# RC_Engine_Sound_ESP32.net
KiCad netlist of a schematic drawn in EAGLE
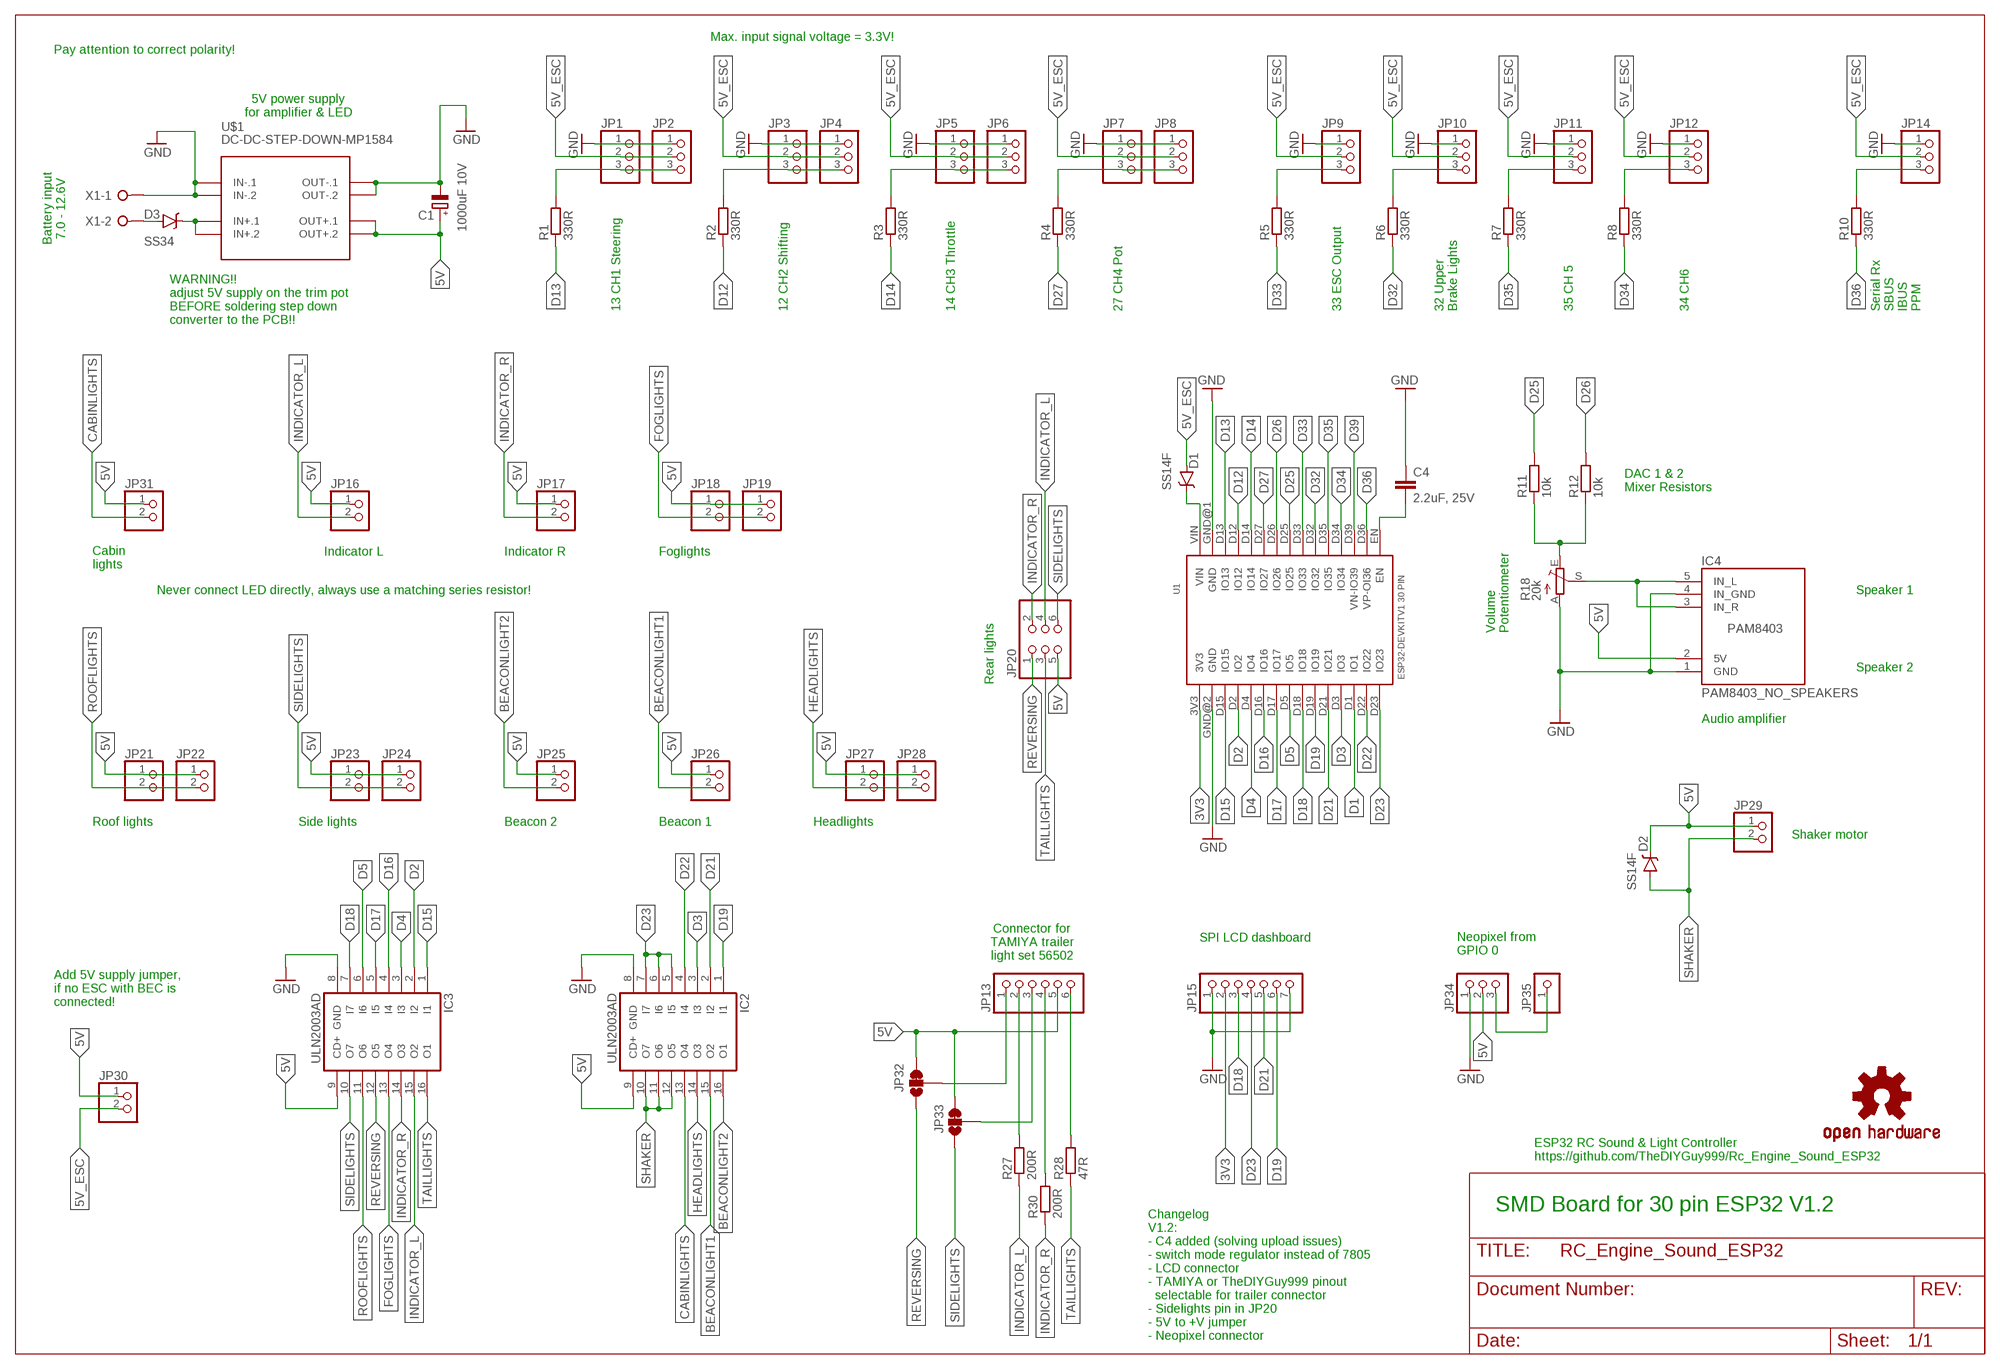
[diagram p0: schematic, sheet 1]

(export (version "E")
  (design (tool "Eeschema 10.0.6"))
  (components
    (comp (ref "C1")
      (value "1000uF 10V")
      (footprint "eagle-import:UD-10X10_NICHICON")
      (libsource (lib "eagle-import") (part "CPOL-EUUD-10X10"))
    )
    (comp (ref "C4")
      (value "2.2uF, 25V")
      (footprint "eagle-import:C1206")
      (libsource (lib "eagle-import") (part "C-EUC1206"))
    )
    (comp (ref "D1")
      (value "SS14F")
      (footprint "eagle-import:SMA-DIODE")
      (libsource (lib "eagle-import") (part "MBRA140"))
    )
    (comp (ref "D2")
      (value "SS14F")
      (footprint "eagle-import:SMA-DIODE")
      (libsource (lib "eagle-import") (part "MBRA140"))
    )
    (comp (ref "D3")
      (value "SS34")
      (footprint "eagle-import:SMA-DIODE")
      (libsource (lib "eagle-import") (part "MBRA140"))
    )
    (comp (ref "IC2")
      (value "ULN2003AD")
      (footprint "eagle-import:SO16")
      (libsource (lib "eagle-import") (part "ULN2003AD"))
    )
    (comp (ref "IC3")
      (value "ULN2003AD")
      (footprint "eagle-import:SO16")
      (libsource (lib "eagle-import") (part "ULN2003AD"))
    )
    (comp (ref "IC4")
      (value "PAM8403_NO_SPEAKERS")
      (footprint "eagle-import:PAM8403_NO_SPEAKERS")
      (libsource (lib "eagle-import") (part "PAM8403_NO_SPEAKERS"))
    )
    (comp (ref "JP1")
      (value "PINHD-1X3")
      (footprint "eagle-import:1X03")
      (libsource (lib "eagle-import") (part "PINHD-1X3"))
    )
    (comp (ref "JP2")
      (value "PINHD-1X3")
      (footprint "eagle-import:1X03")
      (libsource (lib "eagle-import") (part "PINHD-1X3"))
    )
    (comp (ref "JP3")
      (value "PINHD-1X3")
      (footprint "eagle-import:1X03")
      (libsource (lib "eagle-import") (part "PINHD-1X3"))
    )
    (comp (ref "JP4")
      (value "PINHD-1X3")
      (footprint "eagle-import:1X03")
      (libsource (lib "eagle-import") (part "PINHD-1X3"))
    )
    (comp (ref "JP5")
      (value "PINHD-1X3")
      (footprint "eagle-import:1X03")
      (libsource (lib "eagle-import") (part "PINHD-1X3"))
    )
    (comp (ref "JP6")
      (value "PINHD-1X3")
      (footprint "eagle-import:1X03")
      (libsource (lib "eagle-import") (part "PINHD-1X3"))
    )
    (comp (ref "JP7")
      (value "PINHD-1X3")
      (footprint "eagle-import:1X03")
      (libsource (lib "eagle-import") (part "PINHD-1X3"))
    )
    (comp (ref "JP8")
      (value "PINHD-1X3")
      (footprint "eagle-import:1X03")
      (libsource (lib "eagle-import") (part "PINHD-1X3"))
    )
    (comp (ref "JP9")
      (value "PINHD-1X3")
      (footprint "eagle-import:1X03")
      (libsource (lib "eagle-import") (part "PINHD-1X3"))
    )
    (comp (ref "JP10")
      (value "PINHD-1X3")
      (footprint "eagle-import:1X03")
      (libsource (lib "eagle-import") (part "PINHD-1X3"))
    )
    (comp (ref "JP11")
      (value "PINHD-1X3")
      (footprint "eagle-import:1X03")
      (libsource (lib "eagle-import") (part "PINHD-1X3"))
    )
    (comp (ref "JP12")
      (value "PINHD-1X3")
      (footprint "eagle-import:1X03")
      (libsource (lib "eagle-import") (part "PINHD-1X3"))
    )
    (comp (ref "JP13")
      (value "PINHD-1X6")
      (footprint "eagle-import:1X06")
      (libsource (lib "eagle-import") (part "PINHD-1X6"))
    )
    (comp (ref "JP14")
      (value "PINHD-1X3")
      (footprint "eagle-import:1X03")
      (libsource (lib "eagle-import") (part "PINHD-1X3"))
    )
    (comp (ref "JP15")
      (value "PINHD-1X7")
      (footprint "eagle-import:1X07")
      (libsource (lib "eagle-import") (part "PINHD-1X7"))
    )
    (comp (ref "JP16")
      (value "PINHD-1X2")
      (footprint "eagle-import:1X02")
      (libsource (lib "eagle-import") (part "PINHD-1X2"))
    )
    (comp (ref "JP17")
      (value "PINHD-1X2")
      (footprint "eagle-import:1X02")
      (libsource (lib "eagle-import") (part "PINHD-1X2"))
    )
    (comp (ref "JP18")
      (value "PINHD-1X2")
      (footprint "eagle-import:1X02")
      (libsource (lib "eagle-import") (part "PINHD-1X2"))
    )
    (comp (ref "JP19")
      (value "PINHD-1X2")
      (footprint "eagle-import:1X02")
      (libsource (lib "eagle-import") (part "PINHD-1X2"))
    )
    (comp (ref "JP20")
      (value "PINHD-2X3")
      (footprint "eagle-import:2X03")
      (libsource (lib "eagle-import") (part "PINHD-2X3"))
    )
    (comp (ref "JP21")
      (value "PINHD-1X2")
      (footprint "eagle-import:1X02")
      (libsource (lib "eagle-import") (part "PINHD-1X2"))
    )
    (comp (ref "JP22")
      (value "PINHD-1X2")
      (footprint "eagle-import:1X02")
      (libsource (lib "eagle-import") (part "PINHD-1X2"))
    )
    (comp (ref "JP23")
      (value "PINHD-1X2")
      (footprint "eagle-import:1X02")
      (libsource (lib "eagle-import") (part "PINHD-1X2"))
    )
    (comp (ref "JP24")
      (value "PINHD-1X2")
      (footprint "eagle-import:1X02")
      (libsource (lib "eagle-import") (part "PINHD-1X2"))
    )
    (comp (ref "JP25")
      (value "PINHD-1X2")
      (footprint "eagle-import:1X02")
      (libsource (lib "eagle-import") (part "PINHD-1X2"))
    )
    (comp (ref "JP26")
      (value "PINHD-1X2")
      (footprint "eagle-import:1X02")
      (libsource (lib "eagle-import") (part "PINHD-1X2"))
    )
    (comp (ref "JP27")
      (value "PINHD-1X2")
      (footprint "eagle-import:1X02")
      (libsource (lib "eagle-import") (part "PINHD-1X2"))
    )
    (comp (ref "JP28")
      (value "PINHD-1X2")
      (footprint "eagle-import:1X02")
      (libsource (lib "eagle-import") (part "PINHD-1X2"))
    )
    (comp (ref "JP29")
      (value "PINHD-1X2")
      (footprint "eagle-import:1X02")
      (libsource (lib "eagle-import") (part "PINHD-1X2"))
    )
    (comp (ref "JP30")
      (value "PINHD-1X2")
      (footprint "eagle-import:1X02")
      (libsource (lib "eagle-import") (part "PINHD-1X2"))
    )
    (comp (ref "JP31")
      (value "PINHD-1X2")
      (footprint "eagle-import:1X02")
      (libsource (lib "eagle-import") (part "PINHD-1X2"))
    )
    (comp (ref "JP32")
      (value "JUMPER-PAD-3-2OF3_NC_BY_TRACE_LARGE")
      (footprint "eagle-import:PAD-JUMPER-3-2OF3_NC_BY_TRACE_YES_SILK_LARGE")
      (libsource (lib "eagle-import") (part "JUMPER-PAD-3-2OF3_NC_BY_TRACE_LARGE"))
    )
    (comp (ref "JP33")
      (value "JUMPER-PAD-3-2OF3_NC_BY_TRACE_LARGE")
      (footprint "eagle-import:PAD-JUMPER-3-2OF3_NC_BY_TRACE_YES_SILK_LARGE")
      (libsource (lib "eagle-import") (part "JUMPER-PAD-3-2OF3_NC_BY_TRACE_LARGE"))
    )
    (comp (ref "JP34")
      (value "PINHD-1X3")
      (footprint "eagle-import:1X03")
      (libsource (lib "eagle-import") (part "PINHD-1X3"))
    )
    (comp (ref "JP35")
      (value "PINHD-1X1")
      (footprint "eagle-import:1X01")
      (libsource (lib "eagle-import") (part "PINHD-1X1"))
    )
    (comp (ref "LOGO1")
      (value "OSHW-LOGOM")
      (footprint "eagle-import:OSHW-LOGO-M")
      (libsource (lib "eagle-import") (part "OSHW-LOGOM"))
    )
    (comp (ref "R1")
      (value "330R")
      (footprint "eagle-import:R0805")
      (libsource (lib "eagle-import") (part "R-EU_R0805"))
    )
    (comp (ref "R2")
      (value "330R")
      (footprint "eagle-import:R0805")
      (libsource (lib "eagle-import") (part "R-EU_R0805"))
    )
    (comp (ref "R3")
      (value "330R")
      (footprint "eagle-import:R0805")
      (libsource (lib "eagle-import") (part "R-EU_R0805"))
    )
    (comp (ref "R4")
      (value "330R")
      (footprint "eagle-import:R0805")
      (libsource (lib "eagle-import") (part "R-EU_R0805"))
    )
    (comp (ref "R5")
      (value "330R")
      (footprint "eagle-import:R0805")
      (libsource (lib "eagle-import") (part "R-EU_R0805"))
    )
    (comp (ref "R6")
      (value "330R")
      (footprint "eagle-import:R0805")
      (libsource (lib "eagle-import") (part "R-EU_R0805"))
    )
    (comp (ref "R7")
      (value "330R")
      (footprint "eagle-import:R0805")
      (libsource (lib "eagle-import") (part "R-EU_R0805"))
    )
    (comp (ref "R8")
      (value "330R")
      (footprint "eagle-import:R0805")
      (libsource (lib "eagle-import") (part "R-EU_R0805"))
    )
    (comp (ref "R10")
      (value "330R")
      (footprint "eagle-import:R0805")
      (libsource (lib "eagle-import") (part "R-EU_R0805"))
    )
    (comp (ref "R11")
      (value "10k")
      (footprint "eagle-import:R0805")
      (libsource (lib "eagle-import") (part "R-EU_R0805"))
    )
    (comp (ref "R12")
      (value "10k")
      (footprint "eagle-import:R0805")
      (libsource (lib "eagle-import") (part "R-EU_R0805"))
    )
    (comp (ref "R18")
      (value "20k")
      (footprint "eagle-import:S64W")
      (libsource (lib "eagle-import") (part "TRIM_EU-S64W"))
    )
    (comp (ref "R27")
      (value "200R")
      (footprint "eagle-import:R0805")
      (libsource (lib "eagle-import") (part "R-EU_R0805"))
    )
    (comp (ref "R28")
      (value "47R")
      (footprint "eagle-import:R0805")
      (libsource (lib "eagle-import") (part "R-EU_R0805"))
    )
    (comp (ref "R30")
      (value "200R")
      (footprint "eagle-import:R0805")
      (libsource (lib "eagle-import") (part "R-EU_R0805"))
    )
    (comp (ref "U$1")
      (value "DC-DC-STEP-DOWN-MP1584")
      (footprint "eagle-import:DC-DC-STEP-DOWN-MP1584")
      (libsource (lib "eagle-import") (part "DC-DC-STEP-DOWN-MP1584"))
    )
    (comp (ref "U1")
      (value "ESP32DEVKITV1")
      (footprint "eagle-import:ESP32-DEVKITV1")
      (libsource (lib "eagle-import") (part "ESP32DEVKITV1"))
    )
    (comp (ref "X1")
      (value "W237-02P")
      (footprint "eagle-import:W237-132")
      (libsource (lib "eagle-import") (part "W237-02P"))
    )
  )
  (nets
    (net (code "1") (name "3V3") (class "Default")
      (node (ref "JP15") (pin "2") (pinfunction "2_2") (pintype "passive"))
      (node (ref "U1") (pin "3V3") (pinfunction "3V3_3V3") (pintype "power_in"))
    )
    (net (code "2") (name "5V") (class "Default")
      (node (ref "C1") (pin "+") (pinfunction "+_+") (pintype "passive"))
      (node (ref "D2") (pin "C") (pinfunction "C_C") (pintype "passive"))
      (node (ref "IC2") (pin "9") (pinfunction "CD+_9") (pintype "passive"))
      (node (ref "IC3") (pin "9") (pinfunction "CD+_9") (pintype "passive"))
      (node (ref "IC4") (pin "2") (pinfunction "5V_2") (pintype "input"))
      (node (ref "JP13") (pin "5") (pinfunction "5_5") (pintype "passive"))
      (node (ref "JP16") (pin "1") (pinfunction "1_1") (pintype "passive"))
      (node (ref "JP17") (pin "1") (pinfunction "1_1") (pintype "passive"))
      (node (ref "JP18") (pin "1") (pinfunction "1_1") (pintype "passive"))
      (node (ref "JP19") (pin "1") (pinfunction "1_1") (pintype "passive"))
      (node (ref "JP20") (pin "5") (pinfunction "5_5") (pintype "passive"))
      (node (ref "JP21") (pin "1") (pinfunction "1_1") (pintype "passive"))
      (node (ref "JP22") (pin "1") (pinfunction "1_1") (pintype "passive"))
      (node (ref "JP23") (pin "1") (pinfunction "1_1") (pintype "passive"))
      (node (ref "JP24") (pin "1") (pinfunction "1_1") (pintype "passive"))
      (node (ref "JP25") (pin "1") (pinfunction "1_1") (pintype "passive"))
      (node (ref "JP26") (pin "1") (pinfunction "1_1") (pintype "passive"))
      (node (ref "JP27") (pin "1") (pinfunction "1_1") (pintype "passive"))
      (node (ref "JP28") (pin "1") (pinfunction "1_1") (pintype "passive"))
      (node (ref "JP29") (pin "1") (pinfunction "1_1") (pintype "passive"))
      (node (ref "JP30") (pin "1") (pinfunction "1_1") (pintype "passive"))
      (node (ref "JP31") (pin "1") (pinfunction "1_1") (pintype "passive"))
      (node (ref "JP32") (pin "3") (pinfunction "3_3") (pintype "passive"))
      (node (ref "JP33") (pin "3") (pinfunction "3_3") (pintype "passive"))
      (node (ref "JP34") (pin "2") (pinfunction "2_2") (pintype "passive"))
      (node (ref "U$1") (pin "OUT+.1") (pinfunction "OUT+.1_OUT+.1") (pintype "bidirectional"))
      (node (ref "U$1") (pin "OUT+.2") (pinfunction "OUT+.2_OUT+.2") (pintype "bidirectional"))
    )
    (net (code "3") (name "5V_ESC") (class "Default")
      (node (ref "D1") (pin "A") (pinfunction "A_A") (pintype "passive"))
      (node (ref "JP1") (pin "2") (pinfunction "2_2") (pintype "passive"))
      (node (ref "JP10") (pin "2") (pinfunction "2_2") (pintype "passive"))
      (node (ref "JP11") (pin "2") (pinfunction "2_2") (pintype "passive"))
      (node (ref "JP12") (pin "2") (pinfunction "2_2") (pintype "passive"))
      (node (ref "JP14") (pin "2") (pinfunction "2_2") (pintype "passive"))
      (node (ref "JP2") (pin "2") (pinfunction "2_2") (pintype "passive"))
      (node (ref "JP3") (pin "2") (pinfunction "2_2") (pintype "passive"))
      (node (ref "JP30") (pin "2") (pinfunction "2_2") (pintype "passive"))
      (node (ref "JP4") (pin "2") (pinfunction "2_2") (pintype "passive"))
      (node (ref "JP5") (pin "2") (pinfunction "2_2") (pintype "passive"))
      (node (ref "JP6") (pin "2") (pinfunction "2_2") (pintype "passive"))
      (node (ref "JP7") (pin "2") (pinfunction "2_2") (pintype "passive"))
      (node (ref "JP8") (pin "2") (pinfunction "2_2") (pintype "passive"))
      (node (ref "JP9") (pin "2") (pinfunction "2_2") (pintype "passive"))
    )
    (net (code "4") (name "BEACONLIGHT1") (class "Default")
      (node (ref "IC2") (pin "15") (pinfunction "O2_15") (pintype "open_collector"))
      (node (ref "JP26") (pin "2") (pinfunction "2_2") (pintype "passive"))
    )
    (net (code "5") (name "BEACONLIGHT2") (class "Default")
      (node (ref "IC2") (pin "16") (pinfunction "O1_16") (pintype "open_collector"))
      (node (ref "JP25") (pin "2") (pinfunction "2_2") (pintype "passive"))
    )
    (net (code "6") (name "CABINLIGHTS") (class "Default")
      (node (ref "IC2") (pin "13") (pinfunction "O4_13") (pintype "open_collector"))
      (node (ref "JP31") (pin "2") (pinfunction "2_2") (pintype "passive"))
    )
    (net (code "7") (name "D1") (class "Default")
      (node (ref "U1") (pin "D1") (pinfunction "IO1_D1") (pintype "bidirectional"))
    )
    (net (code "8") (name "D2") (class "Default")
      (node (ref "IC3") (pin "2") (pinfunction "I2_2") (pintype "input"))
      (node (ref "U1") (pin "D2") (pinfunction "IO2_D2") (pintype "bidirectional"))
    )
    (net (code "9") (name "D3") (class "Default")
      (node (ref "IC2") (pin "3") (pinfunction "I3_3") (pintype "input"))
      (node (ref "U1") (pin "D3") (pinfunction "IO3_D3") (pintype "bidirectional"))
    )
    (net (code "10") (name "D4") (class "Default")
      (node (ref "IC3") (pin "3") (pinfunction "I3_3") (pintype "input"))
      (node (ref "U1") (pin "D4") (pinfunction "IO4_D4") (pintype "bidirectional"))
    )
    (net (code "11") (name "D5") (class "Default")
      (node (ref "IC3") (pin "6") (pinfunction "I6_6") (pintype "input"))
      (node (ref "U1") (pin "D5") (pinfunction "IO5_D5") (pintype "bidirectional"))
    )
    (net (code "12") (name "D12") (class "Default")
      (node (ref "R2") (pin "1") (pinfunction "1_1") (pintype "passive"))
      (node (ref "U1") (pin "D12") (pinfunction "IO12_D12") (pintype "bidirectional"))
    )
    (net (code "13") (name "D13") (class "Default")
      (node (ref "R1") (pin "1") (pinfunction "1_1") (pintype "passive"))
      (node (ref "U1") (pin "D13") (pinfunction "IO13_D13") (pintype "bidirectional"))
    )
    (net (code "14") (name "D14") (class "Default")
      (node (ref "R3") (pin "1") (pinfunction "1_1") (pintype "passive"))
      (node (ref "U1") (pin "D14") (pinfunction "IO14_D14") (pintype "bidirectional"))
    )
    (net (code "15") (name "D15") (class "Default")
      (node (ref "IC3") (pin "1") (pinfunction "I1_1") (pintype "input"))
      (node (ref "U1") (pin "D15") (pinfunction "IO15_D15") (pintype "bidirectional"))
    )
    (net (code "16") (name "D16") (class "Default")
      (node (ref "IC3") (pin "4") (pinfunction "I4_4") (pintype "input"))
      (node (ref "U1") (pin "D16") (pinfunction "IO16_D16") (pintype "bidirectional"))
    )
    (net (code "17") (name "D17") (class "Default")
      (node (ref "IC3") (pin "5") (pinfunction "I5_5") (pintype "input"))
      (node (ref "U1") (pin "D17") (pinfunction "IO17_D17") (pintype "bidirectional"))
    )
    (net (code "18") (name "D18") (class "Default")
      (node (ref "IC3") (pin "7") (pinfunction "I7_7") (pintype "input"))
      (node (ref "JP15") (pin "3") (pinfunction "3_3") (pintype "passive"))
      (node (ref "U1") (pin "D18") (pinfunction "IO18_D18") (pintype "bidirectional"))
    )
    (net (code "19") (name "D19") (class "Default")
      (node (ref "IC2") (pin "1") (pinfunction "I1_1") (pintype "input"))
      (node (ref "JP15") (pin "6") (pinfunction "6_6") (pintype "passive"))
      (node (ref "U1") (pin "D19") (pinfunction "IO19_D19") (pintype "bidirectional"))
    )
    (net (code "20") (name "D21") (class "Default")
      (node (ref "IC2") (pin "2") (pinfunction "I2_2") (pintype "input"))
      (node (ref "JP15") (pin "5") (pinfunction "5_5") (pintype "passive"))
      (node (ref "U1") (pin "D21") (pinfunction "IO21_D21") (pintype "bidirectional"))
    )
    (net (code "21") (name "D22") (class "Default")
      (node (ref "IC2") (pin "4") (pinfunction "I4_4") (pintype "input"))
      (node (ref "U1") (pin "D22") (pinfunction "IO22_D22") (pintype "bidirectional"))
    )
    (net (code "22") (name "D23") (class "Default")
      (node (ref "IC2") (pin "5") (pinfunction "I5_5") (pintype "input"))
      (node (ref "IC2") (pin "6") (pinfunction "I6_6") (pintype "input"))
      (node (ref "IC2") (pin "7") (pinfunction "I7_7") (pintype "input"))
      (node (ref "JP15") (pin "4") (pinfunction "4_4") (pintype "passive"))
      (node (ref "U1") (pin "D23") (pinfunction "IO23_D23") (pintype "bidirectional"))
    )
    (net (code "23") (name "D25") (class "Default")
      (node (ref "R11") (pin "2") (pinfunction "2_2") (pintype "passive"))
      (node (ref "U1") (pin "D25") (pinfunction "IO25_D25") (pintype "bidirectional"))
    )
    (net (code "24") (name "D26") (class "Default")
      (node (ref "R12") (pin "2") (pinfunction "2_2") (pintype "passive"))
      (node (ref "U1") (pin "D26") (pinfunction "IO26_D26") (pintype "bidirectional"))
    )
    (net (code "25") (name "D27") (class "Default")
      (node (ref "R4") (pin "1") (pinfunction "1_1") (pintype "passive"))
      (node (ref "U1") (pin "D27") (pinfunction "IO27_D27") (pintype "bidirectional"))
    )
    (net (code "26") (name "D32") (class "Default")
      (node (ref "R6") (pin "1") (pinfunction "1_1") (pintype "passive"))
      (node (ref "U1") (pin "D32") (pinfunction "IO32_D32") (pintype "bidirectional"))
    )
    (net (code "27") (name "D33") (class "Default")
      (node (ref "R5") (pin "1") (pinfunction "1_1") (pintype "passive"))
      (node (ref "U1") (pin "D33") (pinfunction "IO33_D33") (pintype "bidirectional"))
    )
    (net (code "28") (name "D34") (class "Default")
      (node (ref "R8") (pin "1") (pinfunction "1_1") (pintype "passive"))
      (node (ref "U1") (pin "D34") (pinfunction "IO34_D34") (pintype "bidirectional"))
    )
    (net (code "29") (name "D35") (class "Default")
      (node (ref "R7") (pin "1") (pinfunction "1_1") (pintype "passive"))
      (node (ref "U1") (pin "D35") (pinfunction "IO35_D35") (pintype "bidirectional"))
    )
    (net (code "30") (name "D36") (class "Default")
      (node (ref "R10") (pin "1") (pinfunction "1_1") (pintype "passive"))
      (node (ref "U1") (pin "D36") (pinfunction "VP-OI36_D36") (pintype "bidirectional"))
    )
    (net (code "31") (name "D39") (class "Default")
      (node (ref "U1") (pin "D39") (pinfunction "VN-IO39_D39") (pintype "bidirectional"))
    )
    (net (code "32") (name "FOGLIGHTS") (class "Default")
      (node (ref "IC3") (pin "13") (pinfunction "O4_13") (pintype "open_collector"))
      (node (ref "JP18") (pin "2") (pinfunction "2_2") (pintype "passive"))
      (node (ref "JP19") (pin "2") (pinfunction "2_2") (pintype "passive"))
    )
    (net (code "33") (name "GND") (class "Default")
      (node (ref "C1") (pin "-") (pinfunction "-_-") (pintype "passive"))
      (node (ref "C4") (pin "1") (pinfunction "1_1") (pintype "passive"))
      (node (ref "IC2") (pin "8") (pinfunction "GND_8") (pintype "power_in"))
      (node (ref "IC3") (pin "8") (pinfunction "GND_8") (pintype "power_in"))
      (node (ref "IC4") (pin "1") (pinfunction "GND_1") (pintype "input"))
      (node (ref "IC4") (pin "4") (pinfunction "IN_GND_4") (pintype "input"))
      (node (ref "JP1") (pin "1") (pinfunction "1_1") (pintype "passive"))
      (node (ref "JP10") (pin "1") (pinfunction "1_1") (pintype "passive"))
      (node (ref "JP11") (pin "1") (pinfunction "1_1") (pintype "passive"))
      (node (ref "JP12") (pin "1") (pinfunction "1_1") (pintype "passive"))
      (node (ref "JP14") (pin "1") (pinfunction "1_1") (pintype "passive"))
      (node (ref "JP15") (pin "1") (pinfunction "1_1") (pintype "passive"))
      (node (ref "JP15") (pin "7") (pinfunction "7_7") (pintype "passive"))
      (node (ref "JP2") (pin "1") (pinfunction "1_1") (pintype "passive"))
      (node (ref "JP3") (pin "1") (pinfunction "1_1") (pintype "passive"))
      (node (ref "JP34") (pin "1") (pinfunction "1_1") (pintype "passive"))
      (node (ref "JP4") (pin "1") (pinfunction "1_1") (pintype "passive"))
      (node (ref "JP5") (pin "1") (pinfunction "1_1") (pintype "passive"))
      (node (ref "JP6") (pin "1") (pinfunction "1_1") (pintype "passive"))
      (node (ref "JP7") (pin "1") (pinfunction "1_1") (pintype "passive"))
      (node (ref "JP8") (pin "1") (pinfunction "1_1") (pintype "passive"))
      (node (ref "JP9") (pin "1") (pinfunction "1_1") (pintype "passive"))
      (node (ref "R18") (pin "A") (pinfunction "A_A") (pintype "passive"))
      (node (ref "U$1") (pin "IN-.1") (pinfunction "IN-.1_IN-.1") (pintype "bidirectional"))
      (node (ref "U$1") (pin "IN-.2") (pinfunction "IN-.2_IN-.2") (pintype "bidirectional"))
      (node (ref "U$1") (pin "OUT-.1") (pinfunction "OUT-.1_OUT-.1") (pintype "bidirectional"))
      (node (ref "U$1") (pin "OUT-.2") (pinfunction "OUT-.2_OUT-.2") (pintype "bidirectional"))
      (node (ref "U1") (pin "GND@1") (pinfunction "GND_GND@1") (pintype "power_in"))
      (node (ref "U1") (pin "GND@2") (pinfunction "GND_GND@2") (pintype "power_in"))
      (node (ref "X1") (pin "1") (pinfunction "KL_1") (pintype "passive"))
    )
    (net (code "34") (name "HEADLIGHTS") (class "Default")
      (node (ref "IC2") (pin "14") (pinfunction "O3_14") (pintype "open_collector"))
      (node (ref "JP27") (pin "2") (pinfunction "2_2") (pintype "passive"))
      (node (ref "JP28") (pin "2") (pinfunction "2_2") (pintype "passive"))
    )
    (net (code "35") (name "INDICATOR_L") (class "Default")
      (node (ref "IC3") (pin "15") (pinfunction "O2_15") (pintype "open_collector"))
      (node (ref "JP16") (pin "2") (pinfunction "2_2") (pintype "passive"))
      (node (ref "JP20") (pin "4") (pinfunction "4_4") (pintype "passive"))
      (node (ref "R27") (pin "1") (pinfunction "1_1") (pintype "passive"))
    )
    (net (code "36") (name "INDICATOR_R") (class "Default")
      (node (ref "IC3") (pin "14") (pinfunction "O3_14") (pintype "open_collector"))
      (node (ref "JP17") (pin "2") (pinfunction "2_2") (pintype "passive"))
      (node (ref "JP20") (pin "2") (pinfunction "2_2") (pintype "passive"))
      (node (ref "R30") (pin "1") (pinfunction "1_1") (pintype "passive"))
    )
    (net (code "37") (name "Net-(C4-Pad2)") (class "Default")
      (node (ref "C4") (pin "2") (pinfunction "2_2") (pintype "passive"))
      (node (ref "U1") (pin "EN") (pinfunction "EN_EN") (pintype "bidirectional"))
    )
    (net (code "38") (name "Net-(D1-PadC)") (class "Default")
      (node (ref "D1") (pin "C") (pinfunction "C_C") (pintype "passive"))
      (node (ref "U1") (pin "VIN") (pinfunction "VIN_VIN") (pintype "power_in"))
    )
    (net (code "39") (name "Net-(D3-PadC)") (class "Default")
      (node (ref "D3") (pin "C") (pinfunction "C_C") (pintype "passive"))
      (node (ref "U$1") (pin "IN+.1") (pinfunction "IN+.1_IN+.1") (pintype "bidirectional"))
      (node (ref "U$1") (pin "IN+.2") (pinfunction "IN+.2_IN+.2") (pintype "bidirectional"))
    )
    (net (code "40") (name "Net-(IC4-IN_L)") (class "Default")
      (node (ref "IC4") (pin "3") (pinfunction "IN_R_3") (pintype "input"))
      (node (ref "IC4") (pin "5") (pinfunction "IN_L_5") (pintype "input"))
      (node (ref "R18") (pin "S") (pinfunction "S_S") (pintype "passive"))
    )
    (net (code "41") (name "Net-(JP1-Pad3)") (class "Default")
      (node (ref "JP1") (pin "3") (pinfunction "3_3") (pintype "passive"))
      (node (ref "JP2") (pin "3") (pinfunction "3_3") (pintype "passive"))
      (node (ref "R1") (pin "2") (pinfunction "2_2") (pintype "passive"))
    )
    (net (code "42") (name "Net-(JP3-Pad3)") (class "Default")
      (node (ref "JP3") (pin "3") (pinfunction "3_3") (pintype "passive"))
      (node (ref "JP4") (pin "3") (pinfunction "3_3") (pintype "passive"))
      (node (ref "R2") (pin "2") (pinfunction "2_2") (pintype "passive"))
    )
    (net (code "43") (name "Net-(JP5-Pad3)") (class "Default")
      (node (ref "JP5") (pin "3") (pinfunction "3_3") (pintype "passive"))
      (node (ref "JP6") (pin "3") (pinfunction "3_3") (pintype "passive"))
      (node (ref "R3") (pin "2") (pinfunction "2_2") (pintype "passive"))
    )
    (net (code "44") (name "Net-(JP7-Pad3)") (class "Default")
      (node (ref "JP7") (pin "3") (pinfunction "3_3") (pintype "passive"))
      (node (ref "JP8") (pin "3") (pinfunction "3_3") (pintype "passive"))
      (node (ref "R4") (pin "2") (pinfunction "2_2") (pintype "passive"))
    )
    (net (code "45") (name "Net-(JP9-Pad3)") (class "Default")
      (node (ref "JP9") (pin "3") (pinfunction "3_3") (pintype "passive"))
      (node (ref "R5") (pin "2") (pinfunction "2_2") (pintype "passive"))
    )
    (net (code "46") (name "Net-(JP10-Pad3)") (class "Default")
      (node (ref "JP10") (pin "3") (pinfunction "3_3") (pintype "passive"))
      (node (ref "R6") (pin "2") (pinfunction "2_2") (pintype "passive"))
    )
    (net (code "47") (name "Net-(JP11-Pad3)") (class "Default")
      (node (ref "JP11") (pin "3") (pinfunction "3_3") (pintype "passive"))
      (node (ref "R7") (pin "2") (pinfunction "2_2") (pintype "passive"))
    )
    (net (code "48") (name "Net-(JP12-Pad3)") (class "Default")
      (node (ref "JP12") (pin "3") (pinfunction "3_3") (pintype "passive"))
      (node (ref "R8") (pin "2") (pinfunction "2_2") (pintype "passive"))
    )
    (net (code "49") (name "Net-(JP13-Pad1)") (class "Default")
      (node (ref "JP13") (pin "1") (pinfunction "1_1") (pintype "passive"))
      (node (ref "JP32") (pin "2") (pinfunction "2_2") (pintype "passive"))
    )
    (net (code "50") (name "Net-(JP13-Pad2)") (class "Default")
      (node (ref "JP13") (pin "2") (pinfunction "2_2") (pintype "passive"))
      (node (ref "R27") (pin "2") (pinfunction "2_2") (pintype "passive"))
    )
    (net (code "51") (name "Net-(JP13-Pad3)") (class "Default")
      (node (ref "JP13") (pin "3") (pinfunction "3_3") (pintype "passive"))
      (node (ref "JP33") (pin "2") (pinfunction "2_2") (pintype "passive"))
    )
    (net (code "52") (name "Net-(JP13-Pad4)") (class "Default")
      (node (ref "JP13") (pin "4") (pinfunction "4_4") (pintype "passive"))
      (node (ref "R30") (pin "2") (pinfunction "2_2") (pintype "passive"))
    )
    (net (code "53") (name "Net-(JP13-Pad6)") (class "Default")
      (node (ref "JP13") (pin "6") (pinfunction "6_6") (pintype "passive"))
      (node (ref "R28") (pin "2") (pinfunction "2_2") (pintype "passive"))
    )
    (net (code "54") (name "Net-(JP14-Pad3)") (class "Default")
      (node (ref "JP14") (pin "3") (pinfunction "3_3") (pintype "passive"))
      (node (ref "R10") (pin "2") (pinfunction "2_2") (pintype "passive"))
    )
    (net (code "55") (name "Net-(JP34-Pad3)") (class "Default")
      (node (ref "JP34") (pin "3") (pinfunction "3_3") (pintype "passive"))
      (node (ref "JP35") (pin "1") (pinfunction "1_1") (pintype "passive"))
    )
    (net (code "56") (name "Net-(R11-Pad1)") (class "Default")
      (node (ref "R11") (pin "1") (pinfunction "1_1") (pintype "passive"))
      (node (ref "R12") (pin "1") (pinfunction "1_1") (pintype "passive"))
      (node (ref "R18") (pin "E") (pinfunction "E_E") (pintype "passive"))
    )
    (net (code "57") (name "Net-(X1B-KL)") (class "Default")
      (node (ref "D3") (pin "A") (pinfunction "A_A") (pintype "passive"))
      (node (ref "X1") (pin "2") (pinfunction "KL_2") (pintype "passive"))
    )
    (net (code "58") (name "REVERSING") (class "Default")
      (node (ref "IC3") (pin "12") (pinfunction "O5_12") (pintype "open_collector"))
      (node (ref "JP20") (pin "1") (pinfunction "1_1") (pintype "passive"))
      (node (ref "JP32") (pin "1") (pinfunction "1_1") (pintype "passive"))
    )
    (net (code "59") (name "ROOFLIGHTS") (class "Default")
      (node (ref "IC3") (pin "11") (pinfunction "O6_11") (pintype "open_collector"))
      (node (ref "JP21") (pin "2") (pinfunction "2_2") (pintype "passive"))
      (node (ref "JP22") (pin "2") (pinfunction "2_2") (pintype "passive"))
    )
    (net (code "60") (name "SHAKER") (class "Default")
      (node (ref "D2") (pin "A") (pinfunction "A_A") (pintype "passive"))
      (node (ref "IC2") (pin "10") (pinfunction "O7_10") (pintype "open_collector"))
      (node (ref "IC2") (pin "11") (pinfunction "O6_11") (pintype "open_collector"))
      (node (ref "IC2") (pin "12") (pinfunction "O5_12") (pintype "open_collector"))
      (node (ref "JP29") (pin "2") (pinfunction "2_2") (pintype "passive"))
    )
    (net (code "61") (name "SIDELIGHTS") (class "Default")
      (node (ref "IC3") (pin "10") (pinfunction "O7_10") (pintype "open_collector"))
      (node (ref "JP20") (pin "6") (pinfunction "6_6") (pintype "passive"))
      (node (ref "JP23") (pin "2") (pinfunction "2_2") (pintype "passive"))
      (node (ref "JP24") (pin "2") (pinfunction "2_2") (pintype "passive"))
      (node (ref "JP33") (pin "1") (pinfunction "1_1") (pintype "passive"))
    )
    (net (code "62") (name "TAILLIGHTS") (class "Default")
      (node (ref "IC3") (pin "16") (pinfunction "O1_16") (pintype "open_collector"))
      (node (ref "JP20") (pin "3") (pinfunction "3_3") (pintype "passive"))
      (node (ref "R28") (pin "1") (pinfunction "1_1") (pintype "passive"))
    )
  )
)
